# Sheet1.net
KiCad netlist of a schematic drawn in Altium Designer
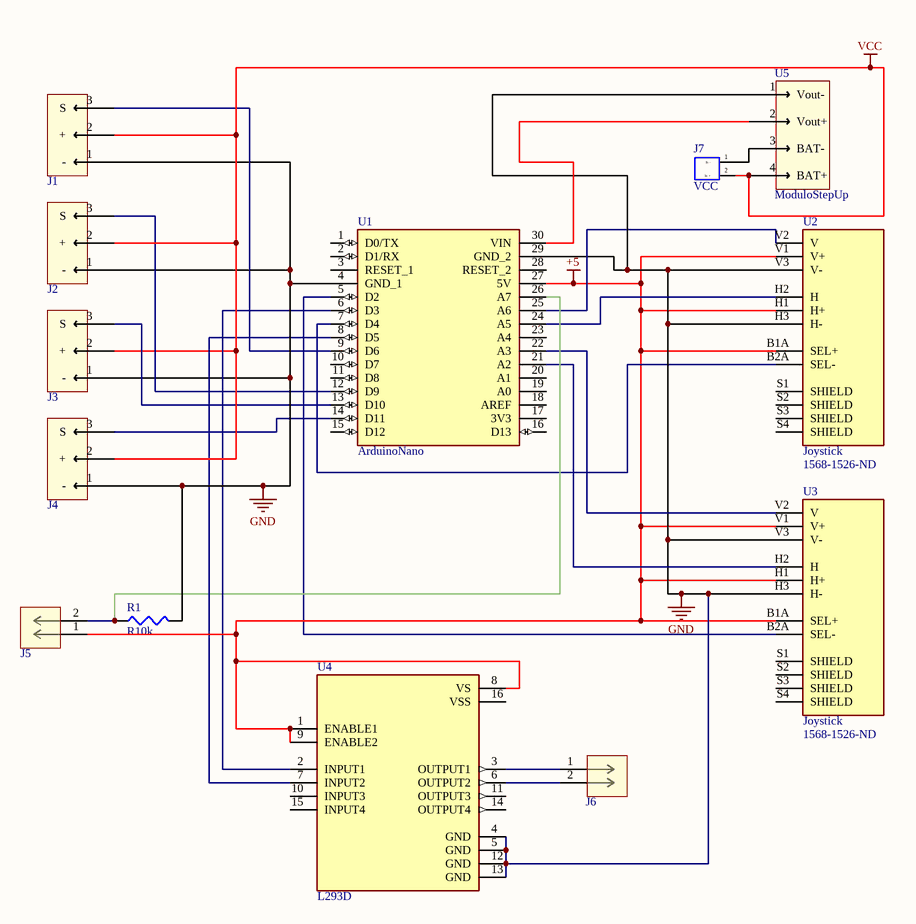
[diagram p0: Sheet1.SchDoc]

(export (version "E")
  (design (tool "Eeschema 10.0.6"))
  (components
    (comp (ref "J1")
      (value "HDR1x3")
      (footprint "HDR1x3")
      (description "THT Vertical Pin Header WR-PHD, Pitch 2.54 mm, Single Row, 3 pins")
      (fields
        (field (name "MANUFACTURER") "Wurth Electronics")
        (field (name "MANUFACTURER PART NUMBER") "61300311121")
      )
      (libsource (lib "Schlib1") (part "H3x1"))
    )
    (comp (ref "J2")
      (value "HDR1x3")
      (footprint "HDR1x3")
      (description "THT Vertical Pin Header WR-PHD, Pitch 2.54 mm, Single Row, 3 pins")
      (fields
        (field (name "MANUFACTURER") "Wurth Electronics")
        (field (name "MANUFACTURER PART NUMBER") "61300311121")
      )
      (libsource (lib "Schlib1") (part "H3x1"))
    )
    (comp (ref "J3")
      (value "HDR1x3")
      (footprint "HDR1x3")
      (description "THT Vertical Pin Header WR-PHD, Pitch 2.54 mm, Single Row, 3 pins")
      (fields
        (field (name "MANUFACTURER") "Wurth Electronics")
        (field (name "MANUFACTURER PART NUMBER") "61300311121")
      )
      (libsource (lib "Schlib1") (part "H3x1"))
    )
    (comp (ref "J4")
      (value "HDR1x3")
      (footprint "HDR1x3")
      (description "THT Vertical Pin Header WR-PHD, Pitch 2.54 mm, Single Row, 3 pins")
      (fields
        (field (name "MANUFACTURER") "Wurth Electronics")
        (field (name "MANUFACTURER PART NUMBER") "61300311121")
      )
      (libsource (lib "Schlib1") (part "H3x1"))
    )
    (comp (ref "J5")
      (value "Header 2x1")
      (footprint "2pin")
      (description "No Description Available")
      (libsource (lib "") (part "H2x1_1"))
    )
    (comp (ref "J6")
      (value "Header 2x1")
      (footprint "2pin")
      (description "No Description Available")
      (libsource (lib "Schlib1") (part "H2x1"))
    )
    (comp (ref "J7") (value "VCC") (footprint "TerminalBlock2Pos") (libsource (lib "Schlib1") (part "Bat")))
    (comp (ref "R1") (value "R10k") (footprint "R10k") (libsource (lib "Schlib1") (part "R10k")))
    (comp (ref "U1")
      (value "ArduinoNano")
      (footprint "ArduinoNano")
      (description "Small, complete, and breadboard-friendly board based on the ATmega328 (Arduino Nano 3.x).")
      (fields (field (name "MP") "A000005") (field (name "MF") "Arduino"))
      (libsource (lib "Schlib1") (part "ArduinoNano"))
    )
    (comp (ref "U2")
      (value "Joystick")
      (footprint "Joystick")
      (description "Thumb Joystick")
      (fields (field (name "MP") "COM-09032") (field (name "SUPPLIER PART NUMBER 1") "1568-1526-ND"))
      (libsource (lib "Schlib1") (part "Joystick"))
    )
    (comp (ref "U3")
      (value "Joystick")
      (footprint "Joystick")
      (description "Thumb Joystick")
      (fields (field (name "MP") "COM-09032") (field (name "SUPPLIER PART NUMBER 1") "1568-1526-ND"))
      (libsource (lib "Schlib1") (part "Joystick"))
    )
    (comp (ref "U4")
      (value "L293D")
      (footprint "L293D")
      (description "Bipolar Motor Driver - Parallel 16-PowerDIP")
      (fields (field (name "MF") "STMicroelectronics"))
      (libsource (lib "Schlib1") (part "L293D"))
    )
    (comp (ref "U5")
      (value "ModuloStepUp")
      (footprint "StepUp")
      (libsource (lib "Schlib1") (part "ModuloStepUp"))
    )
  )
  (nets
    (net (code "1") (name "+5") (class "Default")
      (node (ref "J5") (pin "1") (pinfunction "1_1") (pintype "passive"))
      (node (ref "U1") (pin "27") (pinfunction "5V_27") (pintype "power_in"))
      (node (ref "U2") (pin "B1A") (pinfunction "SEL+_B1A") (pintype "passive"))
      (node (ref "U2") (pin "H1") (pinfunction "H+_H1") (pintype "passive"))
      (node (ref "U2") (pin "V1") (pinfunction "V+_V1") (pintype "passive"))
      (node (ref "U3") (pin "B1A") (pinfunction "SEL+_B1A") (pintype "passive"))
      (node (ref "U3") (pin "H1") (pinfunction "H+_H1") (pintype "passive"))
      (node (ref "U3") (pin "V1") (pinfunction "V+_V1") (pintype "passive"))
      (node (ref "U4") (pin "1") (pinfunction "ENABLE1_1") (pintype "passive"))
      (node (ref "U4") (pin "8") (pinfunction "VS_8") (pintype "power_in"))
      (node (ref "U4") (pin "9") (pinfunction "ENABLE2_9") (pintype "passive"))
    )
    (net (code "2") (name "GND") (class "Default")
      (node (ref "J1") (pin "1") (pinfunction "-_1") (pintype "passive"))
      (node (ref "J2") (pin "1") (pinfunction "-_1") (pintype "passive"))
      (node (ref "J3") (pin "1") (pinfunction "-_1") (pintype "passive"))
      (node (ref "J4") (pin "1") (pinfunction "-_1") (pintype "passive"))
      (node (ref "R1") (pin "2") (pinfunction "2_2") (pintype "passive"))
      (node (ref "U1") (pin "29") (pinfunction "GND_2_29") (pintype "power_in"))
      (node (ref "U1") (pin "4") (pinfunction "GND_1_4") (pintype "power_in"))
      (node (ref "U2") (pin "H3") (pinfunction "H-_H3") (pintype "passive"))
      (node (ref "U2") (pin "V3") (pinfunction "V-_V3") (pintype "passive"))
      (node (ref "U3") (pin "H3") (pinfunction "H-_H3") (pintype "passive"))
      (node (ref "U3") (pin "V3") (pinfunction "V-_V3") (pintype "passive"))
      (node (ref "U4") (pin "12") (pinfunction "GND_12") (pintype "power_in"))
      (node (ref "U4") (pin "13") (pinfunction "GND_13") (pintype "power_in"))
      (node (ref "U4") (pin "4") (pinfunction "GND_4") (pintype "power_in"))
      (node (ref "U4") (pin "5") (pinfunction "GND_5") (pintype "power_in"))
      (node (ref "U5") (pin "1") (pinfunction "Vout-_1") (pintype "passive"))
    )
    (net (code "3") (name "Net-(J1-S)") (class "Default")
      (node (ref "J1") (pin "3") (pinfunction "S_3") (pintype "passive"))
      (node (ref "U1") (pin "9") (pinfunction "D6_9") (pintype "bidirectional"))
    )
    (net (code "4") (name "Net-(J2-S)") (class "Default")
      (node (ref "J2") (pin "3") (pinfunction "S_3") (pintype "passive"))
      (node (ref "U1") (pin "12") (pinfunction "D9_12") (pintype "bidirectional"))
    )
    (net (code "5") (name "Net-(J3-S)") (class "Default")
      (node (ref "J3") (pin "3") (pinfunction "S_3") (pintype "passive"))
      (node (ref "U1") (pin "13") (pinfunction "D10_13") (pintype "bidirectional"))
    )
    (net (code "6") (name "Net-(J4-S)") (class "Default")
      (node (ref "J4") (pin "3") (pinfunction "S_3") (pintype "passive"))
      (node (ref "U1") (pin "14") (pinfunction "D11_14") (pintype "bidirectional"))
    )
    (net (code "7") (name "Net-(J7-In_-)") (class "Default")
      (node (ref "J7") (pin "1") (pinfunction "In_-_1") (pintype "passive"))
      (node (ref "U5") (pin "3") (pinfunction "BAT-_3") (pintype "passive"))
    )
    (net (code "8") (name "Net-(U1-A2)") (class "Default")
      (node (ref "U1") (pin "21") (pinfunction "A2_21") (pintype "passive"))
      (node (ref "U3") (pin "H2") (pinfunction "H_H2") (pintype "passive"))
    )
    (net (code "9") (name "Net-(U1-A3)") (class "Default")
      (node (ref "U1") (pin "22") (pinfunction "A3_22") (pintype "passive"))
      (node (ref "U3") (pin "V2") (pinfunction "V_V2") (pintype "passive"))
    )
    (net (code "10") (name "Net-(U1-A5)") (class "Default")
      (node (ref "U1") (pin "24") (pinfunction "A5_24") (pintype "passive"))
      (node (ref "U2") (pin "H2") (pinfunction "H_H2") (pintype "passive"))
    )
    (net (code "11") (name "Net-(U1-A6)") (class "Default")
      (node (ref "U1") (pin "25") (pinfunction "A6_25") (pintype "passive"))
      (node (ref "U2") (pin "V2") (pinfunction "V_V2") (pintype "passive"))
    )
    (net (code "12") (name "Net-(U1-A7)") (class "Default")
      (node (ref "J5") (pin "2") (pinfunction "2_2") (pintype "passive"))
      (node (ref "R1") (pin "1") (pinfunction "1_1") (pintype "passive"))
      (node (ref "U1") (pin "26") (pinfunction "A7_26") (pintype "passive"))
    )
    (net (code "13") (name "Net-(U1-D2)") (class "Default")
      (node (ref "U1") (pin "5") (pinfunction "D2_5") (pintype "bidirectional"))
      (node (ref "U3") (pin "B2A") (pinfunction "SEL-_B2A") (pintype "passive"))
    )
    (net (code "14") (name "Net-(U1-D3)") (class "Default")
      (node (ref "U1") (pin "6") (pinfunction "D3_6") (pintype "bidirectional"))
      (node (ref "U4") (pin "2") (pinfunction "INPUT1_2") (pintype "passive"))
    )
    (net (code "15") (name "Net-(U1-D4)") (class "Default")
      (node (ref "U1") (pin "7") (pinfunction "D4_7") (pintype "bidirectional"))
      (node (ref "U2") (pin "B2A") (pinfunction "SEL-_B2A") (pintype "passive"))
    )
    (net (code "16") (name "Net-(U1-D5)") (class "Default")
      (node (ref "U1") (pin "8") (pinfunction "D5_8") (pintype "bidirectional"))
      (node (ref "U4") (pin "7") (pinfunction "INPUT2_7") (pintype "passive"))
    )
    (net (code "17") (name "Net-(U1-VIN)") (class "Default")
      (node (ref "U1") (pin "30") (pinfunction "VIN_30") (pintype "power_in"))
      (node (ref "U5") (pin "2") (pinfunction "Vout+_2") (pintype "passive"))
    )
    (net (code "18") (name "Net-(U4-OUTPUT1)") (class "Default")
      (node (ref "J6") (pin "1") (pinfunction "1_1") (pintype "passive"))
      (node (ref "U4") (pin "3") (pinfunction "OUTPUT1_3") (pintype "output"))
    )
    (net (code "19") (name "Net-(U4-OUTPUT2)") (class "Default")
      (node (ref "J6") (pin "2") (pinfunction "2_2") (pintype "passive"))
      (node (ref "U4") (pin "6") (pinfunction "OUTPUT2_6") (pintype "output"))
    )
    (net (code "20") (name "VCC") (class "Default")
      (node (ref "J1") (pin "2") (pinfunction "+_2") (pintype "passive"))
      (node (ref "J2") (pin "2") (pinfunction "+_2") (pintype "passive"))
      (node (ref "J3") (pin "2") (pinfunction "+_2") (pintype "passive"))
      (node (ref "J4") (pin "2") (pinfunction "+_2") (pintype "passive"))
      (node (ref "J7") (pin "2") (pinfunction "In_+_2") (pintype "passive"))
      (node (ref "U5") (pin "4") (pinfunction "BAT+_4") (pintype "passive"))
    )
    (net (code "21") (name "unconnected-(U1-3V3-Pad17)") (class "Default")
      (node (ref "U1") (pin "17") (pinfunction "3V3_17") (pintype "power_in"))
    )
    (net (code "22") (name "unconnected-(U1-A0-Pad19)") (class "Default")
      (node (ref "U1") (pin "19") (pinfunction "A0_19") (pintype "passive"))
    )
    (net (code "23") (name "unconnected-(U1-A1-Pad20)") (class "Default")
      (node (ref "U1") (pin "20") (pinfunction "A1_20") (pintype "passive"))
    )
    (net (code "24") (name "unconnected-(U1-A4-Pad23)") (class "Default")
      (node (ref "U1") (pin "23") (pinfunction "A4_23") (pintype "passive"))
    )
    (net (code "25") (name "unconnected-(U1-AREF-Pad18)") (class "Default")
      (node (ref "U1") (pin "18") (pinfunction "AREF_18") (pintype "passive"))
    )
    (net (code "26") (name "unconnected-(U1-D0{slash}TX-Pad1)") (class "Default")
      (node (ref "U1") (pin "1") (pinfunction "D0/TX_1") (pintype "bidirectional"))
    )
    (net (code "27") (name "unconnected-(U1-D1{slash}RX-Pad2)") (class "Default")
      (node (ref "U1") (pin "2") (pinfunction "D1/RX_2") (pintype "bidirectional"))
    )
    (net (code "28") (name "unconnected-(U1-D7-Pad10)") (class "Default")
      (node (ref "U1") (pin "10") (pinfunction "D7_10") (pintype "bidirectional"))
    )
    (net (code "29") (name "unconnected-(U1-D8-Pad11)") (class "Default")
      (node (ref "U1") (pin "11") (pinfunction "D8_11") (pintype "bidirectional"))
    )
    (net (code "30") (name "unconnected-(U1-D12-Pad15)") (class "Default")
      (node (ref "U1") (pin "15") (pinfunction "D12_15") (pintype "bidirectional"))
    )
    (net (code "31") (name "unconnected-(U1-D13-Pad16)") (class "Default")
      (node (ref "U1") (pin "16") (pinfunction "D13_16") (pintype "bidirectional"))
    )
    (net (code "32") (name "unconnected-(U1-RESET_1-Pad3)") (class "Default")
      (node (ref "U1") (pin "3") (pinfunction "RESET_1_3") (pintype "passive"))
    )
    (net (code "33") (name "unconnected-(U1-RESET_2-Pad28)") (class "Default")
      (node (ref "U1") (pin "28") (pinfunction "RESET_2_28") (pintype "passive"))
    )
    (net (code "34") (name "unconnected-(U2-SHIELD-PadS1)") (class "Default")
      (node (ref "U2") (pin "S1") (pinfunction "SHIELD_S1") (pintype "passive"))
    )
    (net (code "35") (name "unconnected-(U2-SHIELD-PadS2)") (class "Default")
      (node (ref "U2") (pin "S2") (pinfunction "SHIELD_S2") (pintype "passive"))
    )
    (net (code "36") (name "unconnected-(U2-SHIELD-PadS3)") (class "Default")
      (node (ref "U2") (pin "S3") (pinfunction "SHIELD_S3") (pintype "passive"))
    )
    (net (code "37") (name "unconnected-(U2-SHIELD-PadS4)") (class "Default")
      (node (ref "U2") (pin "S4") (pinfunction "SHIELD_S4") (pintype "passive"))
    )
    (net (code "38") (name "unconnected-(U3-SHIELD-PadS1)") (class "Default")
      (node (ref "U3") (pin "S1") (pinfunction "SHIELD_S1") (pintype "passive"))
    )
    (net (code "39") (name "unconnected-(U3-SHIELD-PadS2)") (class "Default")
      (node (ref "U3") (pin "S2") (pinfunction "SHIELD_S2") (pintype "passive"))
    )
    (net (code "40") (name "unconnected-(U3-SHIELD-PadS3)") (class "Default")
      (node (ref "U3") (pin "S3") (pinfunction "SHIELD_S3") (pintype "passive"))
    )
    (net (code "41") (name "unconnected-(U3-SHIELD-PadS4)") (class "Default")
      (node (ref "U3") (pin "S4") (pinfunction "SHIELD_S4") (pintype "passive"))
    )
    (net (code "42") (name "unconnected-(U4-INPUT3-Pad10)") (class "Default")
      (node (ref "U4") (pin "10") (pinfunction "INPUT3_10") (pintype "passive"))
    )
    (net (code "43") (name "unconnected-(U4-INPUT4-Pad15)") (class "Default")
      (node (ref "U4") (pin "15") (pinfunction "INPUT4_15") (pintype "passive"))
    )
    (net (code "44") (name "unconnected-(U4-OUTPUT3-Pad11)") (class "Default")
      (node (ref "U4") (pin "11") (pinfunction "OUTPUT3_11") (pintype "output"))
    )
    (net (code "45") (name "unconnected-(U4-OUTPUT4-Pad14)") (class "Default")
      (node (ref "U4") (pin "14") (pinfunction "OUTPUT4_14") (pintype "output"))
    )
    (net (code "46") (name "unconnected-(U4-VSS-Pad16)") (class "Default")
      (node (ref "U4") (pin "16") (pinfunction "VSS_16") (pintype "power_in"))
    )
  )
)
